# 5V_Converter.net
KiCad netlist of a schematic drawn in Altium Designer
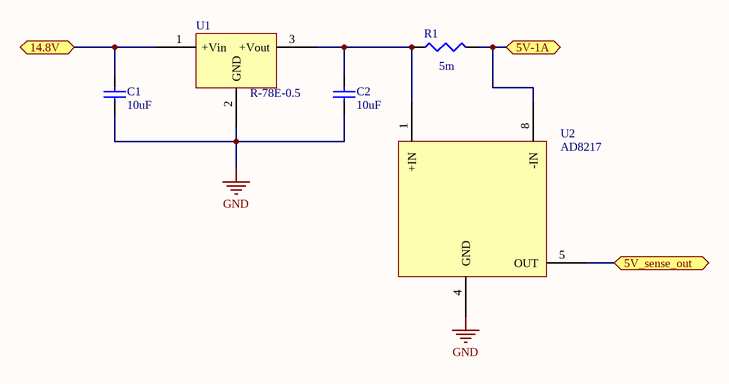
[diagram p0: 5V_Converter.SchDoc]

(export (version "E")
  (design (tool "Eeschema 10.0.6"))
  (components
    (comp (ref "C1")
      (value "10uF")
      (footprint "C1206")
      (description "Capacitor (Semiconductor SIM Model)")
      (fields (field (name "PUBLISHER") "Altium Limited"))
      (libsource (lib "Miscellaneous Devices") (part "Cap Semi"))
    )
    (comp (ref "C2")
      (value "10uF")
      (footprint "C1206")
      (description "Capacitor (Semiconductor SIM Model)")
      (fields (field (name "PUBLISHER") "Altium Limited"))
      (libsource (lib "Miscellaneous Devices") (part "Cap Semi"))
    )
    (comp (ref "R1")
      (value "5m")
      (footprint "J1-0603")
      (description "Resistor")
      (fields (field (name "Comment") "Res3") (field (name "PUBLISHER") "Altium Limited"))
      (libsource (lib "Miscellaneous Devices") (part "Res3"))
    )
    (comp (ref "U1")
      (value "R-78E-0.5")
      (footprint "R-78E-0.5")
      (description "DC/DC Converter")
      (libsource (lib "Integrated_Library") (part "R-78E-0.5"))
    )
    (comp (ref "U2")
      (value "AD8217")
      (footprint "AD8217")
      (description "Current Shunt Moniter")
      (libsource (lib "Integrated_Library") (part "AD8217"))
    )
  )
  (nets
    (net (code "1") (name "/5V-1A") (class "Default")
      (node (ref "R1") (pin "2") (pinfunction "2_2") (pintype "passive"))
      (node (ref "U2") (pin "8") (pinfunction "-IN_8") (pintype "passive"))
    )
    (net (code "2") (name "/5V_sense_out") (class "Default")
      (node (ref "U2") (pin "5") (pinfunction "OUT_5") (pintype "passive"))
    )
    (net (code "3") (name "/14.8V") (class "Default")
      (node (ref "C1") (pin "2") (pinfunction "2_2") (pintype "passive"))
      (node (ref "U1") (pin "1") (pinfunction "+Vin_1") (pintype "passive"))
    )
    (net (code "4") (name "GND") (class "Default")
      (node (ref "C1") (pin "1") (pinfunction "1_1") (pintype "passive"))
      (node (ref "C2") (pin "1") (pinfunction "1_1") (pintype "passive"))
      (node (ref "U1") (pin "2") (pinfunction "GND_2") (pintype "passive"))
      (node (ref "U2") (pin "4") (pinfunction "GND_4") (pintype "passive"))
    )
    (net (code "5") (name "Net-(U1-+Vout)") (class "Default")
      (node (ref "C2") (pin "2") (pinfunction "2_2") (pintype "passive"))
      (node (ref "R1") (pin "1") (pinfunction "1_1") (pintype "passive"))
      (node (ref "U1") (pin "3") (pinfunction "+Vout_3") (pintype "passive"))
      (node (ref "U2") (pin "1") (pinfunction "+IN_1") (pintype "passive"))
    )
  )
)
